# MCPICKUP.net
KiCad netlist of a schematic drawn in EasyEDA
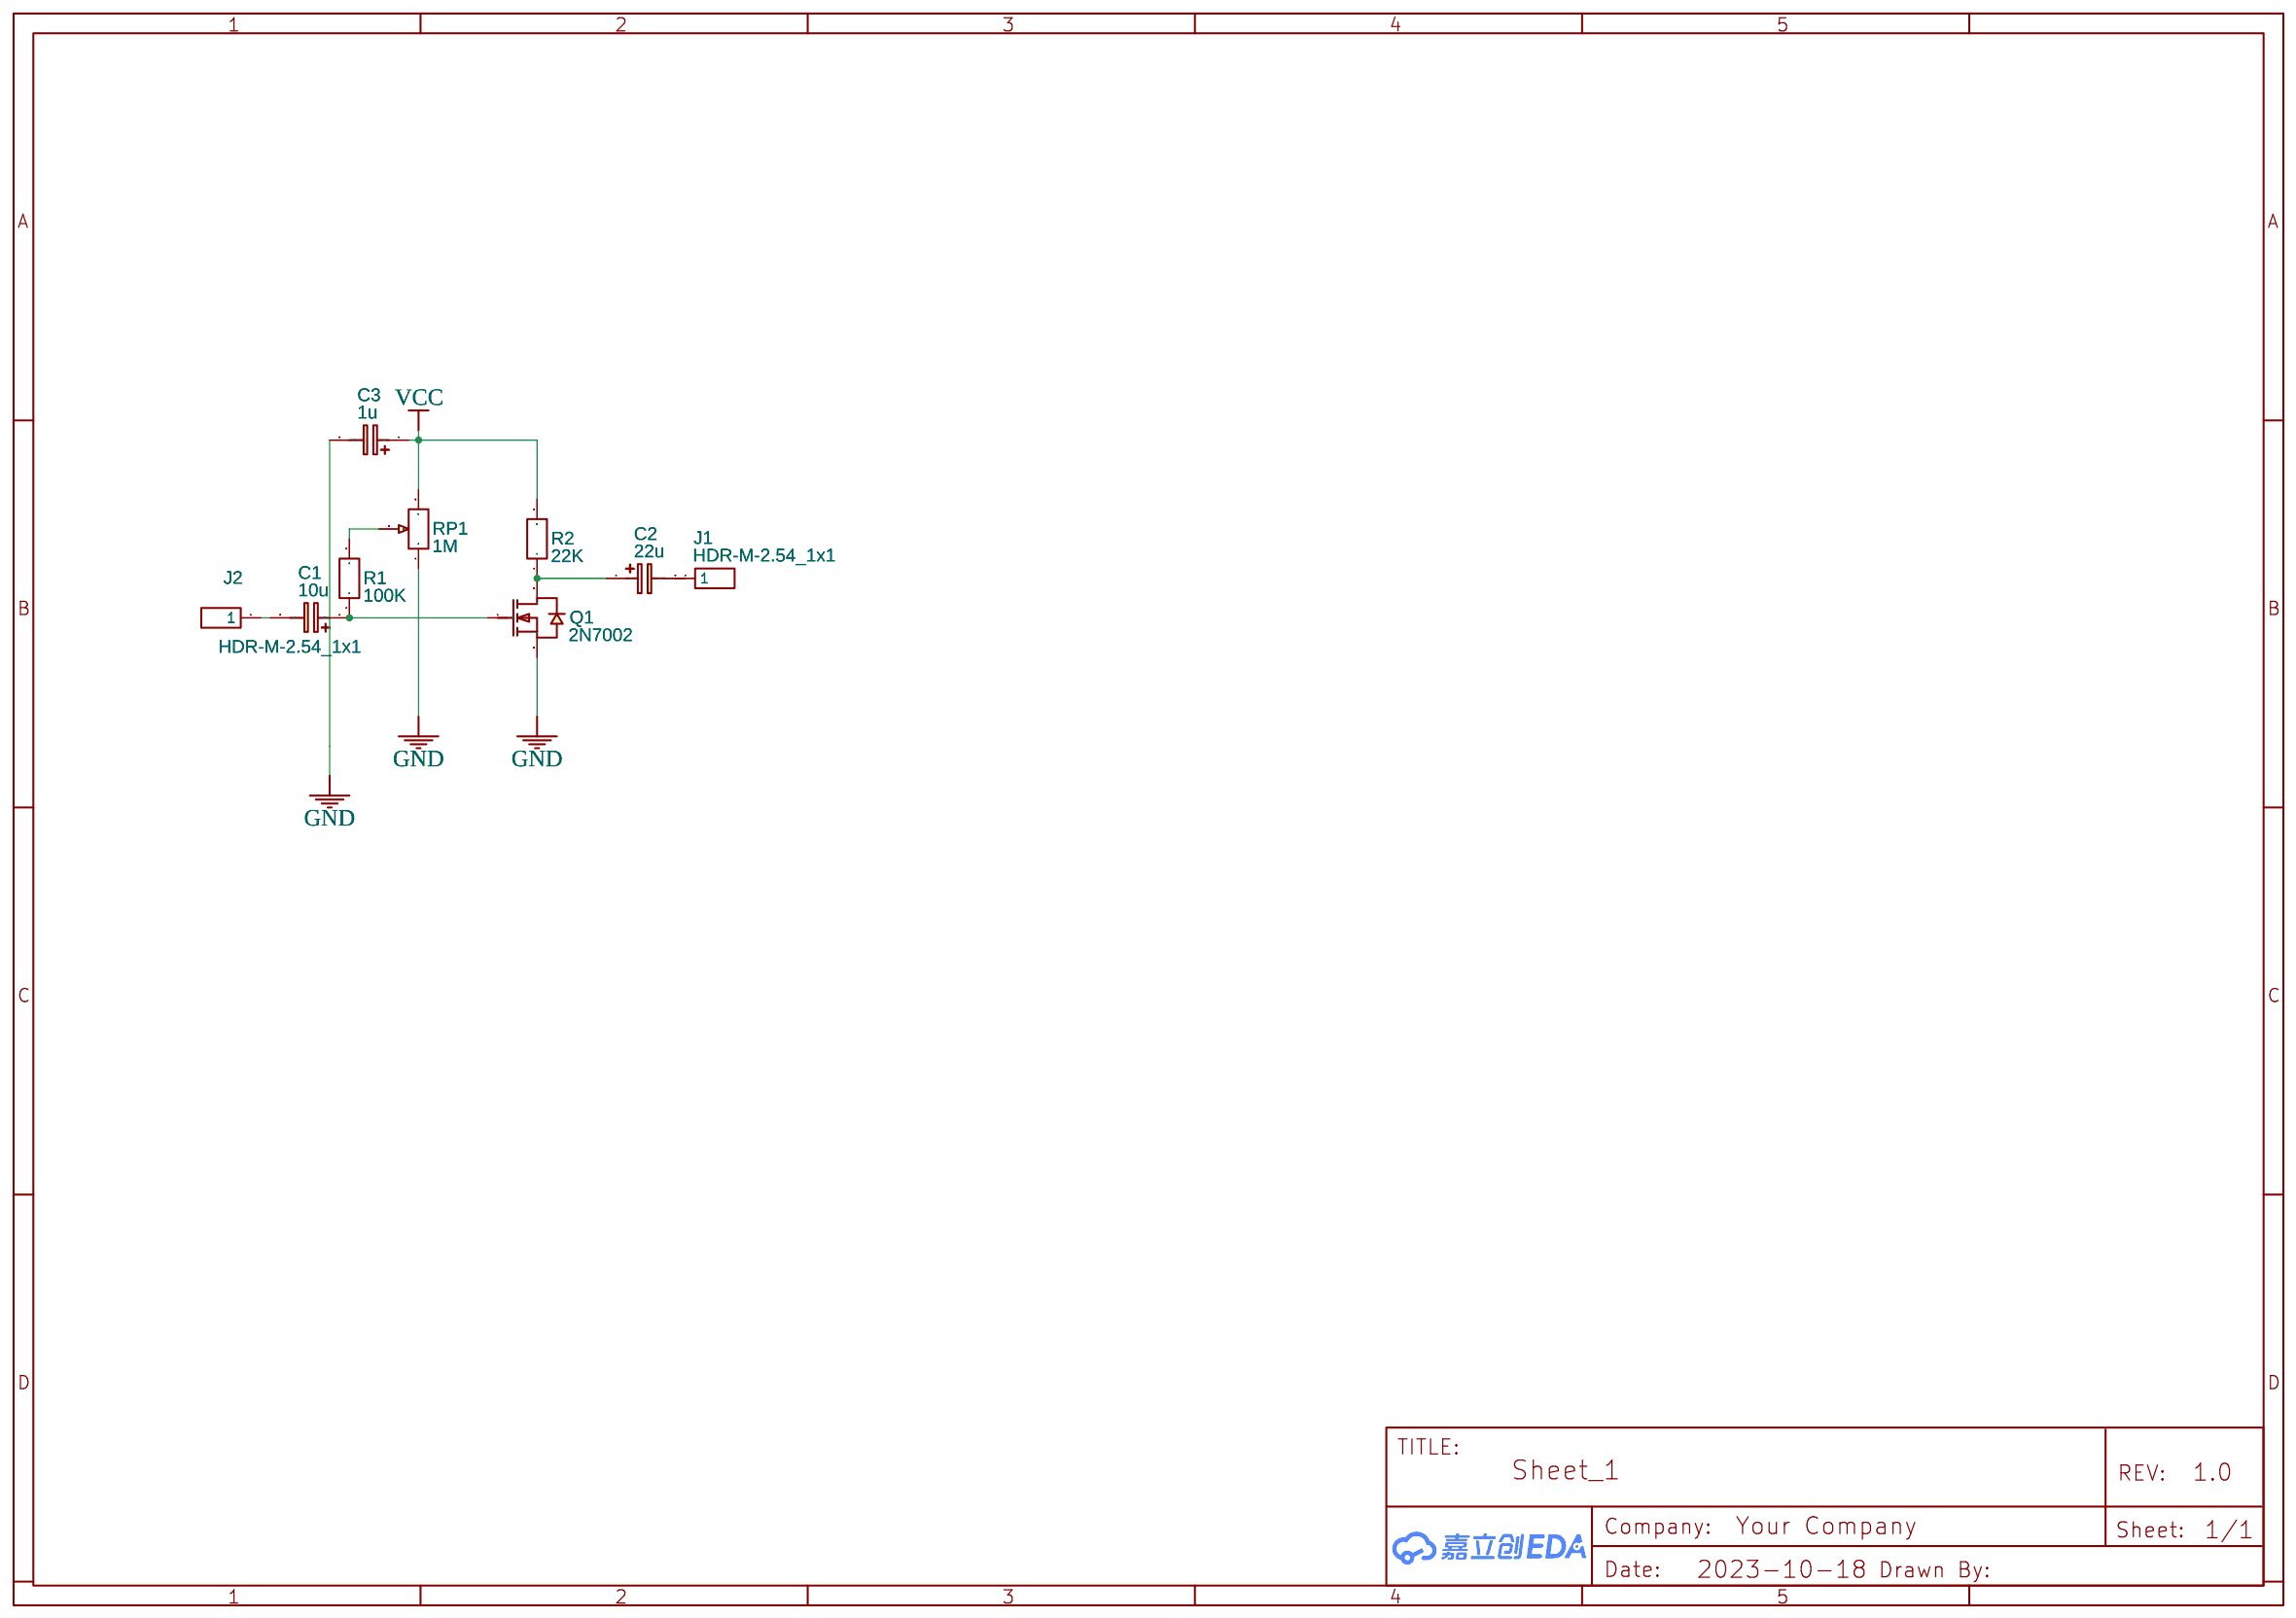
[diagram p0: schematic sheet]

(export (version "E")
  (design (tool "Eeschema 10.0.6"))
  (components
    (comp (ref "C1") (value "10u") (libsource (lib "") (part "C_Tan_SMD_A_EU")))
    (comp (ref "C2") (value "22u") (libsource (lib "") (part "C_Tan_SMD_A_EU_2")))
    (comp (ref "C3") (value "1u") (libsource (lib "") (part "C_Tan_SMD_A_EU_1")))
    (comp (ref "J1")
      (value "HDR-M-2.54_1x1")
      (fields (field (name "BOM_Supplier Part") "C81276"))
      (libsource (lib "") (part "HDR-M-2.54_1x1_1"))
    )
    (comp (ref "J2")
      (value "HDR-M-2.54_1x1")
      (fields (field (name "BOM_Supplier Part") "C81276"))
      (libsource (lib "") (part "HDR-M-2.54_1x1"))
    )
    (comp (ref "Q1")
      (value "2N7002")
      (fields (field (name "BOM_Manufacturer Part") "2N7002,215") (field (name "BOM_Supplier Part") "C65189"))
      (libsource (lib "") (part "2N7002"))
    )
    (comp (ref "R1") (value "100K") (libsource (lib "") (part "R_0603_EU")))
    (comp (ref "R2") (value "22K") (libsource (lib "") (part "R_0603_EU")))
    (comp (ref "RP1") (value "1M") (libsource (lib "") (part "R_3296W_EU")))
  )
  (nets
    (net (code "1") (name "GND") (class "Default")
      (node (ref "C3") (pin "2") (pinfunction "2_2") (pintype "unspecified"))
      (node (ref "Q1") (pin "2") (pinfunction "S_2") (pintype "unspecified"))
      (node (ref "RP1") (pin "1") (pinfunction "1_1") (pintype "input"))
    )
    (net (code "2") (name "Net-(C1-Pad2)") (class "Default")
      (node (ref "C1") (pin "2") (pinfunction "2_2") (pintype "unspecified"))
      (node (ref "J2") (pin "1") (pinfunction "1_1") (pintype "input"))
    )
    (net (code "3") (name "Net-(Q1-D)") (class "Default")
      (node (ref "C2") (pin "1") (pinfunction "1_1") (pintype "unspecified"))
      (node (ref "Q1") (pin "3") (pinfunction "D_3") (pintype "unspecified"))
      (node (ref "R2") (pin "1") (pinfunction "1_1") (pintype "unspecified"))
    )
    (net (code "4") (name "Net-(Q1-G)") (class "Default")
      (node (ref "C1") (pin "1") (pinfunction "1_1") (pintype "unspecified"))
      (node (ref "Q1") (pin "1") (pinfunction "G_1") (pintype "unspecified"))
      (node (ref "R1") (pin "1") (pinfunction "1_1") (pintype "unspecified"))
    )
    (net (code "5") (name "Net-(R1-Pad2)") (class "Default")
      (node (ref "R1") (pin "2") (pinfunction "2_2") (pintype "unspecified"))
      (node (ref "RP1") (pin "2") (pinfunction "2_2") (pintype "input"))
    )
    (net (code "6") (name "VCC") (class "Default")
      (node (ref "C3") (pin "1") (pinfunction "1_1") (pintype "unspecified"))
      (node (ref "R2") (pin "2") (pinfunction "2_2") (pintype "unspecified"))
      (node (ref "RP1") (pin "3") (pinfunction "3_3") (pintype "input"))
    )
    (net (code "7") (name "unconnected-(C2-Pad2)") (class "Default")
      (node (ref "C2") (pin "2") (pinfunction "2_2") (pintype "unspecified"))
    )
    (net (code "8") (name "unconnected-(J1-Pad1)") (class "Default")
      (node (ref "J1") (pin "1") (pinfunction "1_1") (pintype "input"))
    )
  )
)
